# S3C_MuxJTAG.net
KiCad netlist of a schematic drawn in Altium Designer
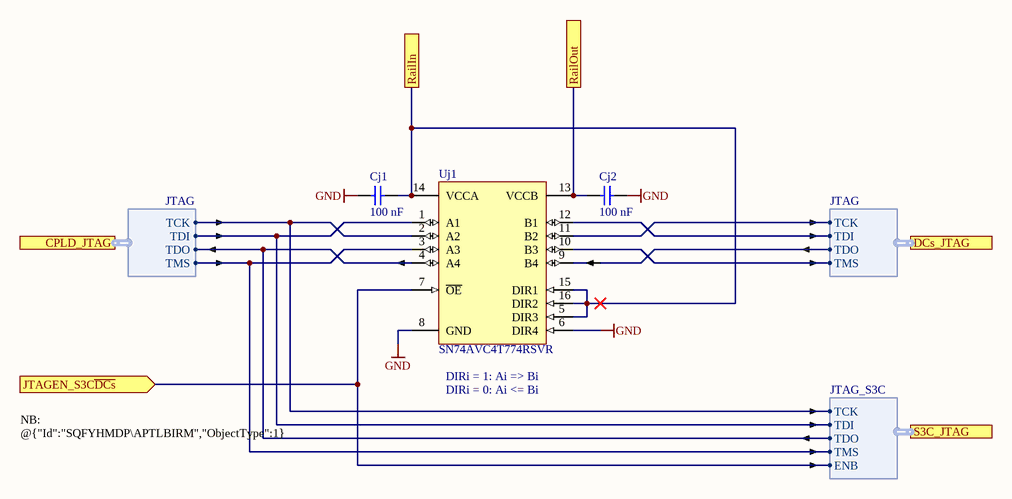
[diagram p0: S3C_MuxJTAG.SchDoc]

(export (version "E")
  (design (tool "Eeschema 10.0.6"))
  (components
    (comp (ref "Cj1")
      (value "100 nF")
      (footprint "C_0603_TE")
      (description "Generic capacitor")
      (fields
        (field (name "TOLERANCE") "10 %")
        (field (name "VOLTAGE") "50 V")
        (field (name "CREATED FROM") "AGeiger")
      )
      (libsource (lib "user") (part "CAP-NP"))
    )
    (comp (ref "Cj2")
      (value "100 nF")
      (footprint "C_0603_TE")
      (description "Generic capacitor")
      (fields
        (field (name "TOLERANCE") "10 %")
        (field (name "VOLTAGE") "50 V")
        (field (name "CREATED FROM") "AGeiger")
      )
      (libsource (lib "user") (part "CAP-NP"))
    )
    (comp (ref "Uj1")
      (value "SN74AVC4T774RSVR")
      (footprint "QFN40P260X180X55-16N")
      (fields
        (field (name "MANUFACTURER") "Texas Instruments")
        (field (name "LCSC PART NUMBER") "C779392")
        (field (name "CREATED FROM") "MGremer")
      )
      (libsource (lib "user") (part "SN74AVC4T774RSVR"))
    )
  )
  (nets
    (net (code "3") (name "/JTAGEN_S3C~{DCs}") (class "Default")
      (node (ref "Uj1") (pin "7") (pinfunction "~{OE}_7") (pintype "input"))
    )
    (net (code "4") (name "/RailIn") (class "Default")
      (node (ref "Cj1") (pin "1") (pinfunction "1_1") (pintype "passive"))
      (node (ref "Uj1") (pin "14") (pinfunction "VCCA_14") (pintype "power_in"))
      (node (ref "Uj1") (pin "15") (pinfunction "DIR1_15") (pintype "input"))
      (node (ref "Uj1") (pin "16") (pinfunction "DIR2_16") (pintype "input"))
      (node (ref "Uj1") (pin "5") (pinfunction "DIR3_5") (pintype "input"))
    )
    (net (code "5") (name "/RailOut") (class "Default")
      (node (ref "Cj2") (pin "2") (pinfunction "2_2") (pintype "passive"))
      (node (ref "Uj1") (pin "13") (pinfunction "VCCB_13") (pintype "power_in"))
    )
    (net (code "8") (name "GND") (class "Default")
      (node (ref "Cj1") (pin "2") (pinfunction "2_2") (pintype "passive"))
      (node (ref "Cj2") (pin "1") (pinfunction "1_1") (pintype "passive"))
      (node (ref "Uj1") (pin "6") (pinfunction "DIR4_6") (pintype "input"))
      (node (ref "Uj1") (pin "8") (pinfunction "GND_8") (pintype "power_in"))
    )
    (net (code "9") (name "unconnected-(Uj1-A1-Pad1)") (class "Default")
      (node (ref "Uj1") (pin "1") (pinfunction "A1_1") (pintype "bidirectional"))
    )
    (net (code "10") (name "unconnected-(Uj1-A2-Pad2)") (class "Default")
      (node (ref "Uj1") (pin "2") (pinfunction "A2_2") (pintype "bidirectional"))
    )
    (net (code "11") (name "unconnected-(Uj1-A3-Pad3)") (class "Default")
      (node (ref "Uj1") (pin "3") (pinfunction "A3_3") (pintype "bidirectional"))
    )
    (net (code "12") (name "unconnected-(Uj1-A4-Pad4)") (class "Default")
      (node (ref "Uj1") (pin "4") (pinfunction "A4_4") (pintype "bidirectional"))
    )
    (net (code "13") (name "unconnected-(Uj1-B1-Pad12)") (class "Default")
      (node (ref "Uj1") (pin "12") (pinfunction "B1_12") (pintype "bidirectional"))
    )
    (net (code "14") (name "unconnected-(Uj1-B2-Pad11)") (class "Default")
      (node (ref "Uj1") (pin "11") (pinfunction "B2_11") (pintype "bidirectional"))
    )
    (net (code "15") (name "unconnected-(Uj1-B3-Pad10)") (class "Default")
      (node (ref "Uj1") (pin "10") (pinfunction "B3_10") (pintype "bidirectional"))
    )
    (net (code "16") (name "unconnected-(Uj1-B4-Pad9)") (class "Default")
      (node (ref "Uj1") (pin "9") (pinfunction "B4_9") (pintype "bidirectional"))
    )
  )
)
